# transceiver_and_pulse_generators.net
KiCad netlist of a schematic drawn in EAGLE
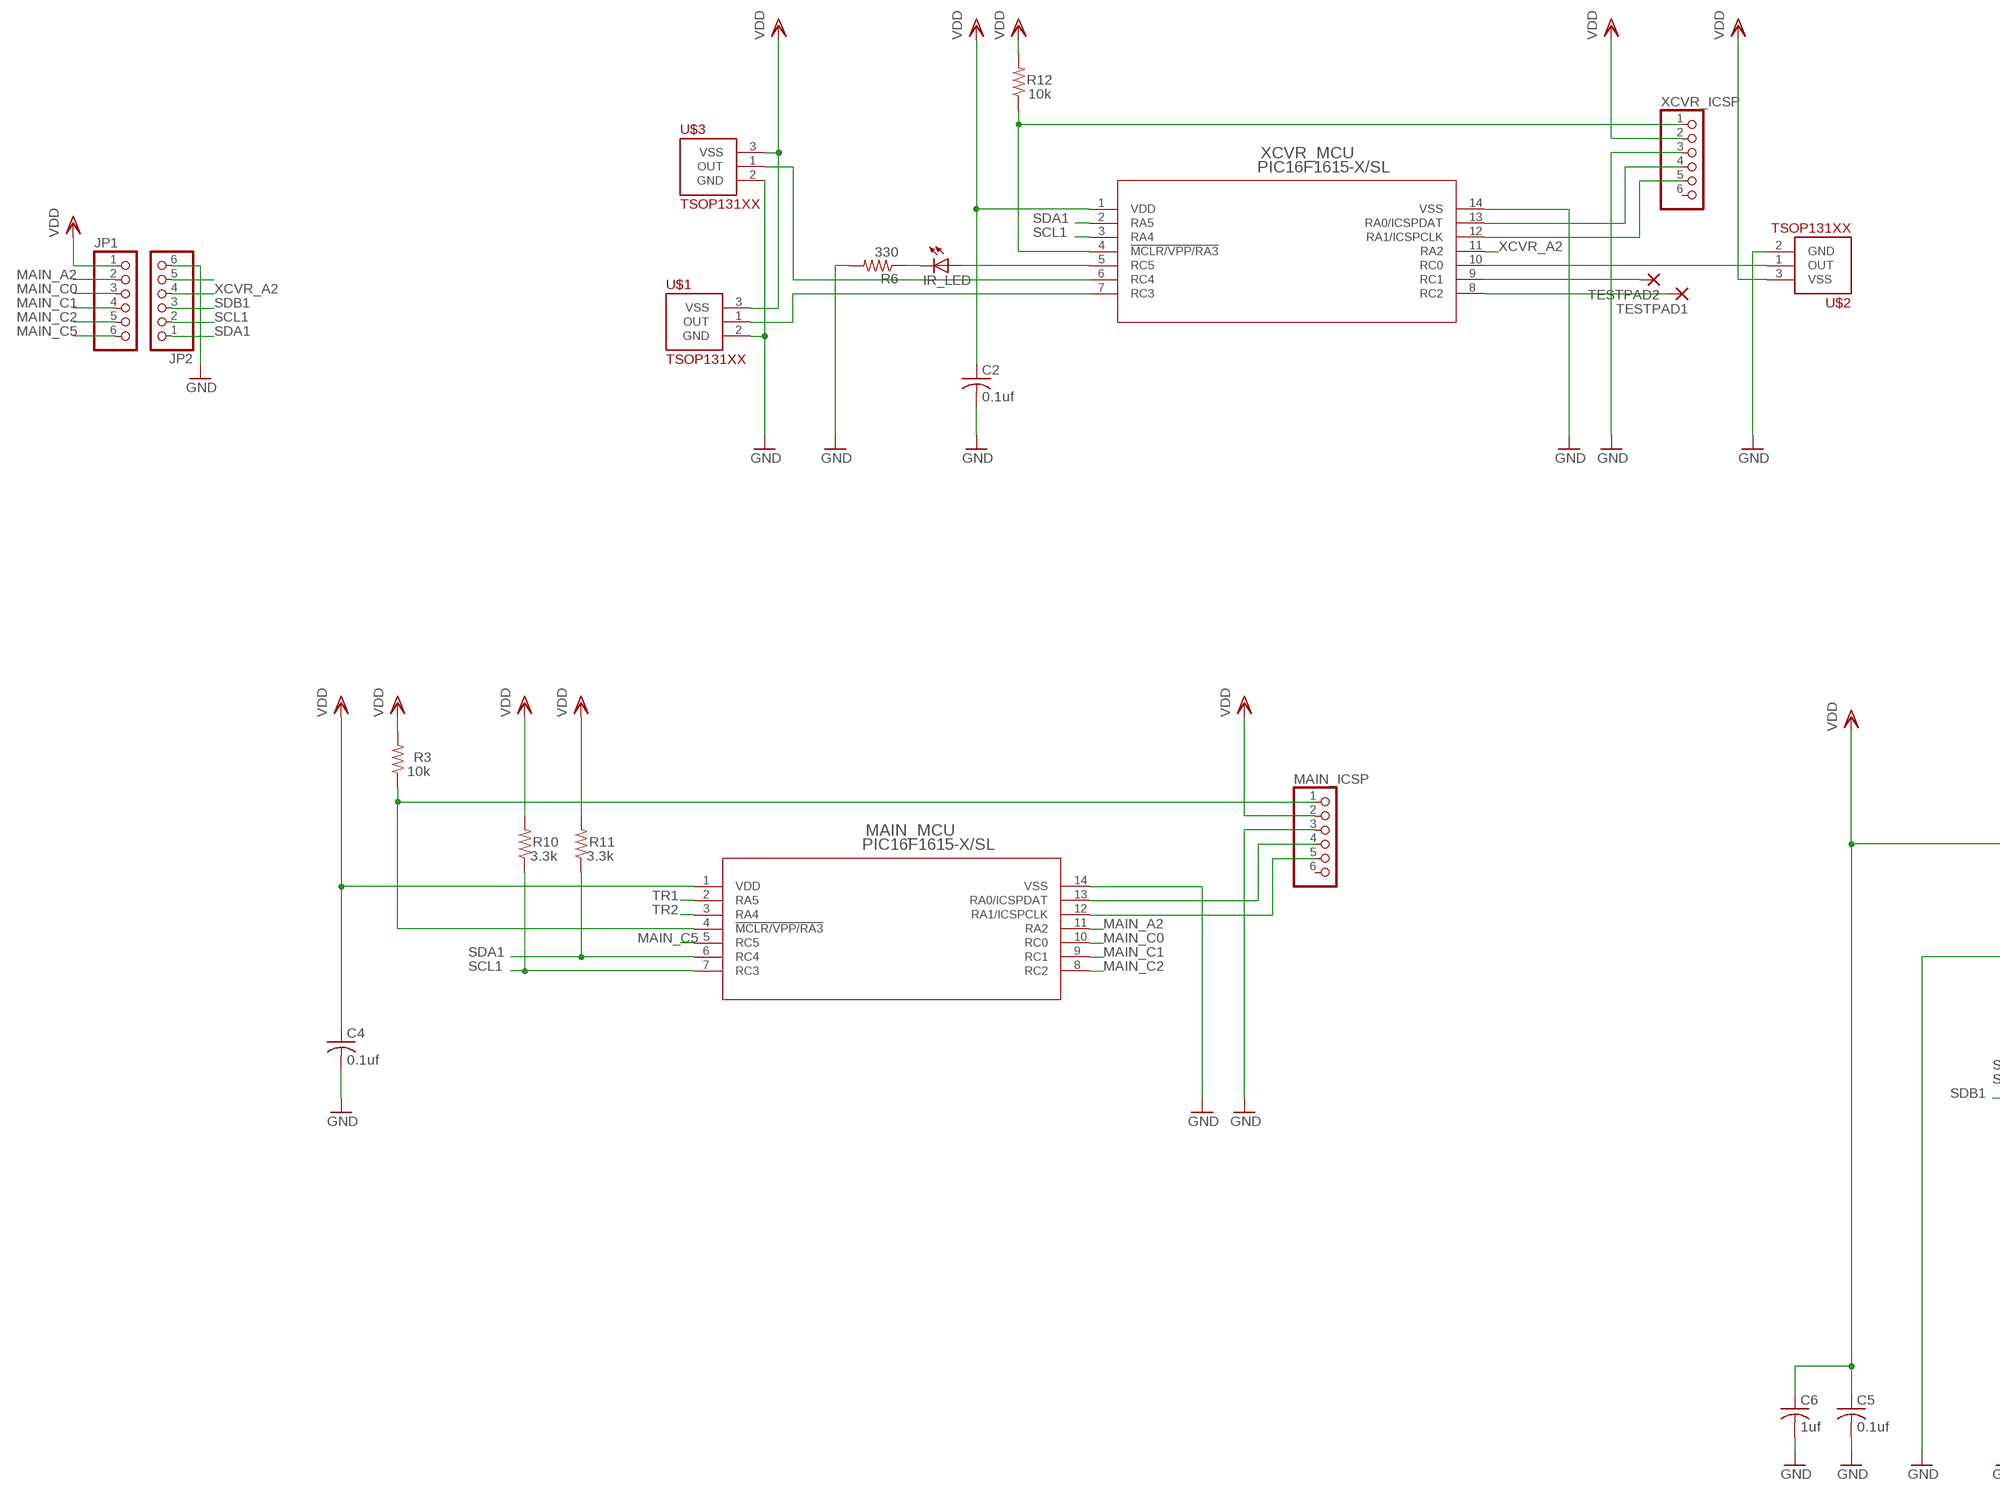
[diagram p0: schematic, sheet 1, part 1 of 2]
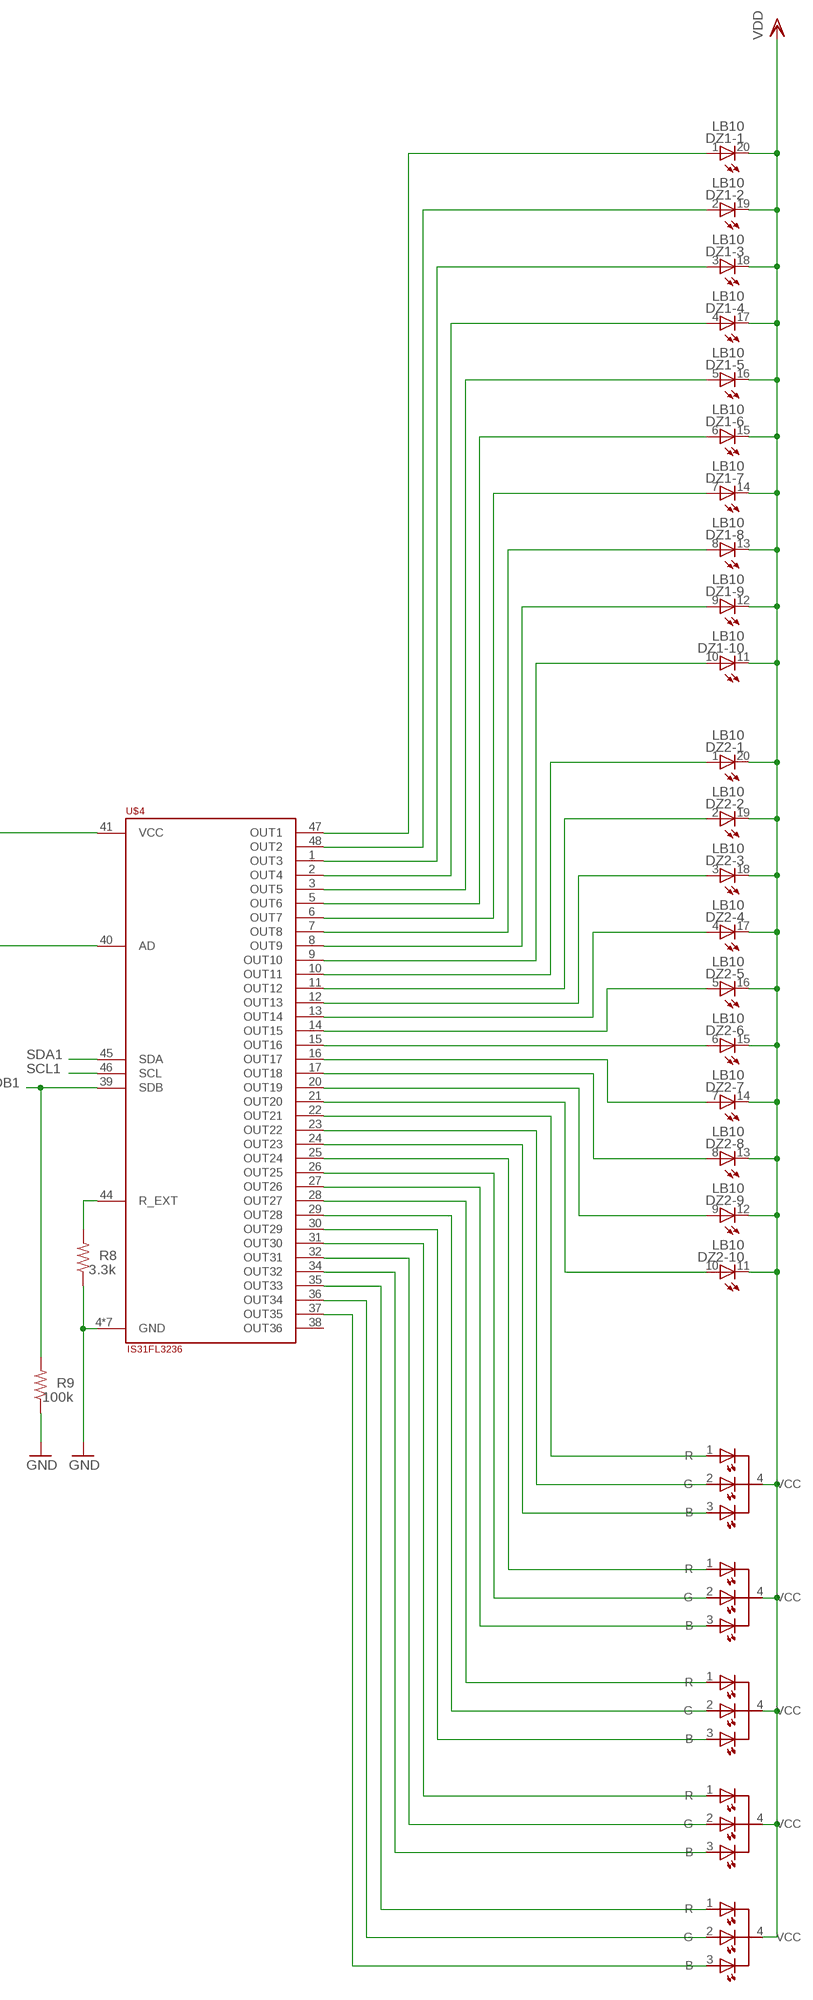
[diagram p1: schematic, sheet 1, part 2 of 2]
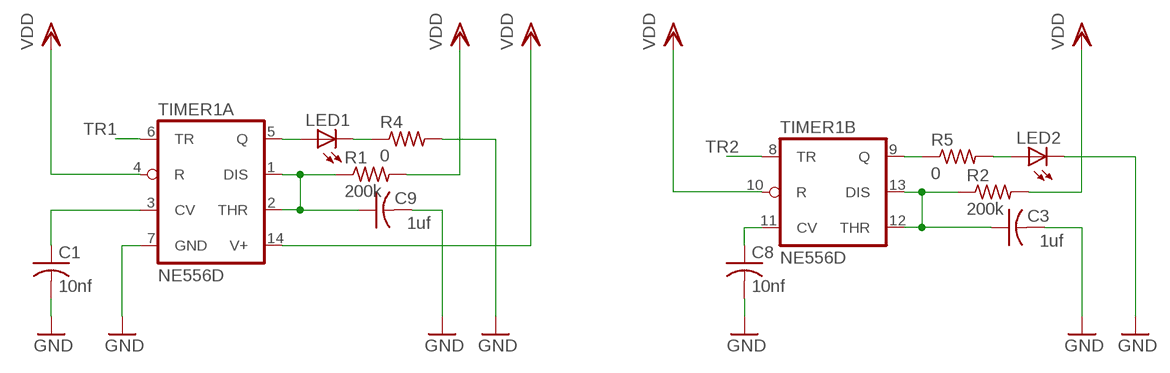
[diagram p2: schematic, sheet 2]

(export (version "E")
  (design (tool "Eeschema 10.0.6"))
  (components
    (comp (ref "C1")
      (value "10nf")
      (footprint "eagle-import:C0603")
      (libsource (lib "eagle-import") (part "C-USC0603"))
    )
    (comp (ref "C3")
      (value "1uf")
      (footprint "eagle-import:C0603")
      (libsource (lib "eagle-import") (part "C-USC0603"))
    )
    (comp (ref "C8")
      (value "10nf")
      (footprint "eagle-import:C0603")
      (libsource (lib "eagle-import") (part "C-USC0603"))
    )
    (comp (ref "C9")
      (value "1uf")
      (footprint "eagle-import:C0603")
      (libsource (lib "eagle-import") (part "C-USC0603"))
    )
    (comp (ref "LED1")
      (value "LED5MM")
      (footprint "eagle-import:LED5MM")
      (libsource (lib "eagle-import") (part "LED5MM"))
    )
    (comp (ref "LED2")
      (value "LED5MM")
      (footprint "eagle-import:LED5MM")
      (libsource (lib "eagle-import") (part "LED5MM"))
    )
    (comp (ref "R1")
      (value "200k")
      (footprint "eagle-import:R0603")
      (libsource (lib "eagle-import") (part "R-US_R0603"))
    )
    (comp (ref "R2")
      (value "200k")
      (footprint "eagle-import:R0603")
      (libsource (lib "eagle-import") (part "R-US_R0603"))
    )
    (comp (ref "R4")
      (value "0")
      (footprint "eagle-import:R0603")
      (libsource (lib "eagle-import") (part "R-US_R0603"))
    )
    (comp (ref "R5")
      (value "0")
      (footprint "eagle-import:R0603")
      (libsource (lib "eagle-import") (part "R-US_R0603"))
    )
    (comp (ref "TIMER1")
      (value "NE556D")
      (footprint "eagle-import:SO14")
      (libsource (lib "eagle-import") (part "556DNE"))
    )
    (comp (ref "C2")
      (value "0.1uf")
      (footprint "eagle-import:C0603")
      (libsource (lib "eagle-import") (part "C-USC0603"))
    )
    (comp (ref "C4")
      (value "0.1uf")
      (footprint "eagle-import:C0603")
      (libsource (lib "eagle-import") (part "C-USC0603"))
    )
    (comp (ref "C5")
      (value "0.1uf")
      (footprint "eagle-import:C0603")
      (libsource (lib "eagle-import") (part "C-USC0603"))
    )
    (comp (ref "C6")
      (value "1uf")
      (footprint "eagle-import:C0603")
      (libsource (lib "eagle-import") (part "C-USC0603"))
    )
    (comp (ref "DZ1")
      (value "LB10")
      (footprint "eagle-import:LB10")
      (libsource (lib "eagle-import") (part "LB10"))
    )
    (comp (ref "DZ2")
      (value "LB10")
      (footprint "eagle-import:LB10")
      (libsource (lib "eagle-import") (part "LB10"))
    )
    (comp (ref "IR_LED")
      (value "LED5MM")
      (footprint "eagle-import:LED5MM")
      (libsource (lib "eagle-import") (part "LED5MM"))
    )
    (comp (ref "JP1")
      (value "PINHD-1X6")
      (footprint "eagle-import:1X06")
      (libsource (lib "eagle-import") (part "PINHD-1X6"))
    )
    (comp (ref "JP2")
      (value "PINHD-1X6")
      (footprint "eagle-import:1X06")
      (libsource (lib "eagle-import") (part "PINHD-1X6"))
    )
    (comp (ref "MAIN_ICSP")
      (value "PINHD-1X6")
      (footprint "eagle-import:1X06")
      (libsource (lib "eagle-import") (part "PINHD-1X6"))
    )
    (comp (ref "MAIN_MCU")
      (value "PIC16F1615-X/SL")
      (footprint "eagle-import:SOIC14_SL")
      (fields (field (name "MANUFACTURER_PART_NUMBER") "pic16f1615xsl"))
      (libsource (lib "eagle-import") (part "PIC16F1615-X/SL"))
    )
    (comp (ref "R3")
      (value "10k")
      (footprint "eagle-import:R0603")
      (libsource (lib "eagle-import") (part "R-US_R0603"))
    )
    (comp (ref "R6")
      (value "330")
      (footprint "eagle-import:R0603")
      (libsource (lib "eagle-import") (part "R-US_R0603"))
    )
    (comp (ref "R8")
      (value "3.3k")
      (footprint "eagle-import:R0603")
      (libsource (lib "eagle-import") (part "R-US_R0603"))
    )
    (comp (ref "R9")
      (value "100k")
      (footprint "eagle-import:R0603")
      (libsource (lib "eagle-import") (part "R-US_R0603"))
    )
    (comp (ref "R10")
      (value "3.3k")
      (footprint "eagle-import:R0603")
      (libsource (lib "eagle-import") (part "R-US_R0603"))
    )
    (comp (ref "R11")
      (value "3.3k")
      (footprint "eagle-import:R0603")
      (libsource (lib "eagle-import") (part "R-US_R0603"))
    )
    (comp (ref "R12")
      (value "10k")
      (footprint "eagle-import:R0603")
      (libsource (lib "eagle-import") (part "R-US_R0603"))
    )
    (comp (ref "TESTPAD1")
      (value "SMD2")
      (footprint "eagle-import:SMD1,27-2,54")
      (libsource (lib "eagle-import") (part "SMD2"))
    )
    (comp (ref "TESTPAD2")
      (value "SMD2")
      (footprint "eagle-import:SMD1,27-2,54")
      (libsource (lib "eagle-import") (part "SMD2"))
    )
    (comp (ref "U$1")
      (value "TSOP131XX")
      (footprint "eagle-import:TSOP13XXX")
      (libsource (lib "eagle-import") (part "TSOP131XX"))
    )
    (comp (ref "U$2")
      (value "TSOP131XX")
      (footprint "eagle-import:TSOP13XXX")
      (libsource (lib "eagle-import") (part "TSOP131XX"))
    )
    (comp (ref "U$3")
      (value "TSOP131XX")
      (footprint "eagle-import:TSOP13XXX")
      (libsource (lib "eagle-import") (part "TSOP131XX"))
    )
    (comp (ref "U$4")
      (value "IS31FL3236")
      (footprint "eagle-import:IS31FL3236")
      (libsource (lib "eagle-import") (part "IS31FL3236"))
    )
    (comp (ref "U$5")
      (value "LTST-C19HE1WT")
      (footprint "eagle-import:LTST-C19HE1WT")
      (libsource (lib "eagle-import") (part "LTST-C19HE1WT"))
    )
    (comp (ref "U$6")
      (value "LTST-C19HE1WT")
      (footprint "eagle-import:LTST-C19HE1WT")
      (libsource (lib "eagle-import") (part "LTST-C19HE1WT"))
    )
    (comp (ref "U$7")
      (value "LTST-C19HE1WT")
      (footprint "eagle-import:LTST-C19HE1WT")
      (libsource (lib "eagle-import") (part "LTST-C19HE1WT"))
    )
    (comp (ref "U$8")
      (value "LTST-C19HE1WT")
      (footprint "eagle-import:LTST-C19HE1WT")
      (libsource (lib "eagle-import") (part "LTST-C19HE1WT"))
    )
    (comp (ref "U$9")
      (value "LTST-C19HE1WT")
      (footprint "eagle-import:LTST-C19HE1WT")
      (libsource (lib "eagle-import") (part "LTST-C19HE1WT"))
    )
    (comp (ref "XCVR_ICSP")
      (value "PINHD-1X6")
      (footprint "eagle-import:1X06")
      (libsource (lib "eagle-import") (part "PINHD-1X6"))
    )
    (comp (ref "XCVR_MCU")
      (value "PIC16F1615-X/SL")
      (footprint "eagle-import:SOIC14_SL")
      (fields (field (name "MANUFACTURER_PART_NUMBER") "pic16f1615xsl"))
      (libsource (lib "eagle-import") (part "PIC16F1615-X/SL"))
    )
  )
  (nets
    (net (code "1") (name "GND") (class "Default")
      (node (ref "C1") (pin "2") (pinfunction "2_2") (pintype "passive"))
      (node (ref "C2") (pin "2") (pinfunction "2_2") (pintype "passive"))
      (node (ref "C3") (pin "2") (pinfunction "2_2") (pintype "passive"))
      (node (ref "C4") (pin "2") (pinfunction "2_2") (pintype "passive"))
      (node (ref "C5") (pin "2") (pinfunction "2_2") (pintype "passive"))
      (node (ref "C6") (pin "2") (pinfunction "2_2") (pintype "passive"))
      (node (ref "C8") (pin "2") (pinfunction "2_2") (pintype "passive"))
      (node (ref "C9") (pin "2") (pinfunction "2_2") (pintype "passive"))
      (node (ref "JP2") (pin "6") (pinfunction "6_6") (pintype "passive"))
      (node (ref "LED2") (pin "K") (pinfunction "C_K") (pintype "passive"))
      (node (ref "MAIN_ICSP") (pin "3") (pinfunction "3_3") (pintype "passive"))
      (node (ref "MAIN_MCU") (pin "14") (pinfunction "VSS_14") (pintype "power_in"))
      (node (ref "R4") (pin "2") (pinfunction "2_2") (pintype "passive"))
      (node (ref "R6") (pin "2") (pinfunction "2_2") (pintype "passive"))
      (node (ref "R8") (pin "1") (pinfunction "1_1") (pintype "passive"))
      (node (ref "R9") (pin "1") (pinfunction "1_1") (pintype "passive"))
      (node (ref "TIMER1") (pin "7") (pinfunction "GND_7") (pintype "power_in"))
      (node (ref "U$1") (pin "2") (pinfunction "GND_2") (pintype "bidirectional"))
      (node (ref "U$2") (pin "2") (pinfunction "GND_2") (pintype "bidirectional"))
      (node (ref "U$3") (pin "2") (pinfunction "GND_2") (pintype "bidirectional"))
      (node (ref "U$4") (pin "18") (pinfunction "GND_18") (pintype "bidirectional"))
      (node (ref "U$4") (pin "19") (pinfunction "GND_19") (pintype "bidirectional"))
      (node (ref "U$4") (pin "33") (pinfunction "GND_33") (pintype "bidirectional"))
      (node (ref "U$4") (pin "4") (pinfunction "GND_4") (pintype "bidirectional"))
      (node (ref "U$4") (pin "40") (pinfunction "AD_40") (pintype "bidirectional"))
      (node (ref "U$4") (pin "42") (pinfunction "GND_42") (pintype "bidirectional"))
      (node (ref "U$4") (pin "43") (pinfunction "GND_43") (pintype "bidirectional"))
      (node (ref "U$4") (pin "49") (pinfunction "GND_49") (pintype "bidirectional"))
      (node (ref "XCVR_ICSP") (pin "3") (pinfunction "3_3") (pintype "passive"))
      (node (ref "XCVR_MCU") (pin "14") (pinfunction "VSS_14") (pintype "power_in"))
    )
    (net (code "2") (name "MAIN_A2") (class "Default")
      (node (ref "JP1") (pin "2") (pinfunction "2_2") (pintype "passive"))
      (node (ref "MAIN_MCU") (pin "11") (pinfunction "RA2_11") (pintype "bidirectional"))
    )
    (net (code "3") (name "MAIN_C0") (class "Default")
      (node (ref "JP1") (pin "3") (pinfunction "3_3") (pintype "passive"))
      (node (ref "MAIN_MCU") (pin "10") (pinfunction "RC0_10") (pintype "bidirectional"))
    )
    (net (code "4") (name "MAIN_C1") (class "Default")
      (node (ref "JP1") (pin "4") (pinfunction "4_4") (pintype "passive"))
      (node (ref "MAIN_MCU") (pin "9") (pinfunction "RC1_9") (pintype "bidirectional"))
    )
    (net (code "5") (name "MAIN_C2") (class "Default")
      (node (ref "JP1") (pin "5") (pinfunction "5_5") (pintype "passive"))
      (node (ref "MAIN_MCU") (pin "8") (pinfunction "RC2_8") (pintype "bidirectional"))
    )
    (net (code "6") (name "MAIN_C5") (class "Default")
      (node (ref "JP1") (pin "6") (pinfunction "6_6") (pintype "passive"))
      (node (ref "MAIN_MCU") (pin "5") (pinfunction "RC5_5") (pintype "bidirectional"))
    )
    (net (code "7") (name "Net-(DZ1A-A)") (class "Default")
      (node (ref "DZ1") (pin "1") (pinfunction "A_1") (pintype "passive"))
      (node (ref "U$4") (pin "47") (pinfunction "OUT1_47") (pintype "bidirectional"))
    )
    (net (code "8") (name "Net-(DZ1B-A)") (class "Default")
      (node (ref "DZ1") (pin "10") (pinfunction "A_10") (pintype "passive"))
      (node (ref "U$4") (pin "9") (pinfunction "OUT10_9") (pintype "bidirectional"))
    )
    (net (code "9") (name "Net-(DZ1C-A)") (class "Default")
      (node (ref "DZ1") (pin "2") (pinfunction "A_2") (pintype "passive"))
      (node (ref "U$4") (pin "48") (pinfunction "OUT2_48") (pintype "bidirectional"))
    )
    (net (code "10") (name "Net-(DZ1D-A)") (class "Default")
      (node (ref "DZ1") (pin "3") (pinfunction "A_3") (pintype "passive"))
      (node (ref "U$4") (pin "1") (pinfunction "OUT3_1") (pintype "bidirectional"))
    )
    (net (code "11") (name "Net-(DZ1E-A)") (class "Default")
      (node (ref "DZ1") (pin "4") (pinfunction "A_4") (pintype "passive"))
      (node (ref "U$4") (pin "2") (pinfunction "OUT4_2") (pintype "bidirectional"))
    )
    (net (code "12") (name "Net-(DZ1F-A)") (class "Default")
      (node (ref "DZ1") (pin "5") (pinfunction "A_5") (pintype "passive"))
      (node (ref "U$4") (pin "3") (pinfunction "OUT5_3") (pintype "bidirectional"))
    )
    (net (code "13") (name "Net-(DZ1G-A)") (class "Default")
      (node (ref "DZ1") (pin "6") (pinfunction "A_6") (pintype "passive"))
      (node (ref "U$4") (pin "5") (pinfunction "OUT6_5") (pintype "bidirectional"))
    )
    (net (code "14") (name "Net-(DZ1H-A)") (class "Default")
      (node (ref "DZ1") (pin "7") (pinfunction "A_7") (pintype "passive"))
      (node (ref "U$4") (pin "6") (pinfunction "OUT7_6") (pintype "bidirectional"))
    )
    (net (code "15") (name "Net-(DZ1I-A)") (class "Default")
      (node (ref "DZ1") (pin "8") (pinfunction "A_8") (pintype "passive"))
      (node (ref "U$4") (pin "7") (pinfunction "OUT8_7") (pintype "bidirectional"))
    )
    (net (code "16") (name "Net-(DZ1J-A)") (class "Default")
      (node (ref "DZ1") (pin "9") (pinfunction "A_9") (pintype "passive"))
      (node (ref "U$4") (pin "8") (pinfunction "OUT9_8") (pintype "bidirectional"))
    )
    (net (code "17") (name "Net-(DZ2A-A)") (class "Default")
      (node (ref "DZ2") (pin "1") (pinfunction "A_1") (pintype "passive"))
      (node (ref "U$4") (pin "10") (pinfunction "OUT11_10") (pintype "bidirectional"))
    )
    (net (code "18") (name "Net-(DZ2B-A)") (class "Default")
      (node (ref "DZ2") (pin "10") (pinfunction "A_10") (pintype "passive"))
      (node (ref "U$4") (pin "21") (pinfunction "OUT20_21") (pintype "bidirectional"))
    )
    (net (code "19") (name "Net-(DZ2C-A)") (class "Default")
      (node (ref "DZ2") (pin "2") (pinfunction "A_2") (pintype "passive"))
      (node (ref "U$4") (pin "11") (pinfunction "OUT12_11") (pintype "bidirectional"))
    )
    (net (code "20") (name "Net-(DZ2D-A)") (class "Default")
      (node (ref "DZ2") (pin "3") (pinfunction "A_3") (pintype "passive"))
      (node (ref "U$4") (pin "12") (pinfunction "OUT13_12") (pintype "bidirectional"))
    )
    (net (code "21") (name "Net-(DZ2E-A)") (class "Default")
      (node (ref "DZ2") (pin "4") (pinfunction "A_4") (pintype "passive"))
      (node (ref "U$4") (pin "13") (pinfunction "OUT14_13") (pintype "bidirectional"))
    )
    (net (code "22") (name "Net-(DZ2F-A)") (class "Default")
      (node (ref "DZ2") (pin "5") (pinfunction "A_5") (pintype "passive"))
      (node (ref "U$4") (pin "14") (pinfunction "OUT15_14") (pintype "bidirectional"))
    )
    (net (code "23") (name "Net-(DZ2G-A)") (class "Default")
      (node (ref "DZ2") (pin "6") (pinfunction "A_6") (pintype "passive"))
      (node (ref "U$4") (pin "15") (pinfunction "OUT16_15") (pintype "bidirectional"))
    )
    (net (code "24") (name "Net-(DZ2H-A)") (class "Default")
      (node (ref "DZ2") (pin "7") (pinfunction "A_7") (pintype "passive"))
      (node (ref "U$4") (pin "16") (pinfunction "OUT17_16") (pintype "bidirectional"))
    )
    (net (code "25") (name "Net-(DZ2I-A)") (class "Default")
      (node (ref "DZ2") (pin "8") (pinfunction "A_8") (pintype "passive"))
      (node (ref "U$4") (pin "17") (pinfunction "OUT18_17") (pintype "bidirectional"))
    )
    (net (code "26") (name "Net-(DZ2J-A)") (class "Default")
      (node (ref "DZ2") (pin "9") (pinfunction "A_9") (pintype "passive"))
      (node (ref "U$4") (pin "20") (pinfunction "OUT19_20") (pintype "bidirectional"))
    )
    (net (code "27") (name "Net-(IR_LED-C)") (class "Default")
      (node (ref "IR_LED") (pin "K") (pinfunction "C_K") (pintype "passive"))
      (node (ref "R6") (pin "1") (pinfunction "1_1") (pintype "passive"))
    )
    (net (code "28") (name "Net-(LED1-C)") (class "Default")
      (node (ref "LED1") (pin "K") (pinfunction "C_K") (pintype "passive"))
      (node (ref "R4") (pin "1") (pinfunction "1_1") (pintype "passive"))
    )
    (net (code "29") (name "Net-(LED2-PadA)") (class "Default")
      (node (ref "LED2") (pin "A") (pinfunction "A_A") (pintype "passive"))
      (node (ref "R5") (pin "2") (pinfunction "2_2") (pintype "passive"))
    )
    (net (code "30") (name "Net-(MAIN_MCU-RA0{slash}ICSPDAT)") (class "Default")
      (node (ref "MAIN_ICSP") (pin "4") (pinfunction "4_4") (pintype "passive"))
      (node (ref "MAIN_MCU") (pin "13") (pinfunction "RA0/ICSPDAT_13") (pintype "bidirectional"))
    )
    (net (code "31") (name "Net-(MAIN_MCU-RA1{slash}ICSPCLK)") (class "Default")
      (node (ref "MAIN_ICSP") (pin "5") (pinfunction "5_5") (pintype "passive"))
      (node (ref "MAIN_MCU") (pin "12") (pinfunction "RA1/ICSPCLK_12") (pintype "bidirectional"))
    )
    (net (code "32") (name "Net-(MAIN_MCU-~{MCLR{slash}VPP{slash}RA3})") (class "Default")
      (node (ref "MAIN_ICSP") (pin "1") (pinfunction "1_1") (pintype "passive"))
      (node (ref "MAIN_MCU") (pin "4") (pinfunction "~{MCLR/VPP/RA3}_4") (pintype "bidirectional"))
      (node (ref "R3") (pin "1") (pinfunction "1_1") (pintype "passive"))
    )
    (net (code "33") (name "Net-(TESTPAD1-P)") (class "Default")
      (node (ref "TESTPAD1") (pin "1") (pinfunction "P_1") (pintype "passive"))
      (node (ref "XCVR_MCU") (pin "8") (pinfunction "RC2_8") (pintype "bidirectional"))
    )
    (net (code "34") (name "Net-(TESTPAD2-P)") (class "Default")
      (node (ref "TESTPAD2") (pin "1") (pinfunction "P_1") (pintype "passive"))
      (node (ref "XCVR_MCU") (pin "9") (pinfunction "RC1_9") (pintype "bidirectional"))
    )
    (net (code "35") (name "Net-(TIMER1A-CV)") (class "Default")
      (node (ref "C1") (pin "1") (pinfunction "1_1") (pintype "passive"))
      (node (ref "TIMER1") (pin "3") (pinfunction "CV_3") (pintype "input"))
    )
    (net (code "36") (name "Net-(TIMER1A-DIS)") (class "Default")
      (node (ref "C9") (pin "1") (pinfunction "1_1") (pintype "passive"))
      (node (ref "R1") (pin "1") (pinfunction "1_1") (pintype "passive"))
      (node (ref "TIMER1") (pin "1") (pinfunction "DIS_1") (pintype "input"))
      (node (ref "TIMER1") (pin "2") (pinfunction "THR_2") (pintype "input"))
    )
    (net (code "37") (name "Net-(TIMER1A-Q)") (class "Default")
      (node (ref "LED1") (pin "A") (pinfunction "A_A") (pintype "passive"))
      (node (ref "TIMER1") (pin "5") (pinfunction "Q_5") (pintype "output"))
    )
    (net (code "38") (name "Net-(TIMER1B-CV)") (class "Default")
      (node (ref "C8") (pin "1") (pinfunction "1_1") (pintype "passive"))
      (node (ref "TIMER1") (pin "11") (pinfunction "CV_11") (pintype "input"))
    )
    (net (code "39") (name "Net-(TIMER1B-DIS)") (class "Default")
      (node (ref "C3") (pin "1") (pinfunction "1_1") (pintype "passive"))
      (node (ref "R2") (pin "1") (pinfunction "1_1") (pintype "passive"))
      (node (ref "TIMER1") (pin "12") (pinfunction "THR_12") (pintype "input"))
      (node (ref "TIMER1") (pin "13") (pinfunction "DIS_13") (pintype "input"))
    )
    (net (code "40") (name "Net-(TIMER1B-Q)") (class "Default")
      (node (ref "R5") (pin "1") (pinfunction "1_1") (pintype "passive"))
      (node (ref "TIMER1") (pin "9") (pinfunction "Q_9") (pintype "output"))
    )
    (net (code "41") (name "Net-(U$1-OUT)") (class "Default")
      (node (ref "U$1") (pin "1") (pinfunction "OUT_1") (pintype "bidirectional"))
      (node (ref "XCVR_MCU") (pin "7") (pinfunction "RC3_7") (pintype "bidirectional"))
    )
    (net (code "42") (name "Net-(U$2-OUT)") (class "Default")
      (node (ref "U$2") (pin "1") (pinfunction "OUT_1") (pintype "bidirectional"))
      (node (ref "XCVR_MCU") (pin "10") (pinfunction "RC0_10") (pintype "bidirectional"))
    )
    (net (code "43") (name "Net-(U$3-OUT)") (class "Default")
      (node (ref "U$3") (pin "1") (pinfunction "OUT_1") (pintype "bidirectional"))
      (node (ref "XCVR_MCU") (pin "6") (pinfunction "RC4_6") (pintype "bidirectional"))
    )
    (net (code "44") (name "Net-(U$4-OUT21)") (class "Default")
      (node (ref "U$4") (pin "22") (pinfunction "OUT21_22") (pintype "bidirectional"))
      (node (ref "U$5") (pin "1") (pinfunction "R_1") (pintype "bidirectional"))
    )
    (net (code "45") (name "Net-(U$4-OUT22)") (class "Default")
      (node (ref "U$4") (pin "23") (pinfunction "OUT22_23") (pintype "bidirectional"))
      (node (ref "U$5") (pin "2") (pinfunction "G_2") (pintype "bidirectional"))
    )
    (net (code "46") (name "Net-(U$4-OUT23)") (class "Default")
      (node (ref "U$4") (pin "24") (pinfunction "OUT23_24") (pintype "bidirectional"))
      (node (ref "U$5") (pin "3") (pinfunction "B_3") (pintype "bidirectional"))
    )
    (net (code "47") (name "Net-(U$4-OUT24)") (class "Default")
      (node (ref "U$4") (pin "25") (pinfunction "OUT24_25") (pintype "bidirectional"))
      (node (ref "U$6") (pin "1") (pinfunction "R_1") (pintype "bidirectional"))
    )
    (net (code "48") (name "Net-(U$4-OUT25)") (class "Default")
      (node (ref "U$4") (pin "26") (pinfunction "OUT25_26") (pintype "bidirectional"))
      (node (ref "U$6") (pin "2") (pinfunction "G_2") (pintype "bidirectional"))
    )
    (net (code "49") (name "Net-(U$4-OUT26)") (class "Default")
      (node (ref "U$4") (pin "27") (pinfunction "OUT26_27") (pintype "bidirectional"))
      (node (ref "U$6") (pin "3") (pinfunction "B_3") (pintype "bidirectional"))
    )
    (net (code "50") (name "Net-(U$4-OUT27)") (class "Default")
      (node (ref "U$4") (pin "28") (pinfunction "OUT27_28") (pintype "bidirectional"))
      (node (ref "U$7") (pin "1") (pinfunction "R_1") (pintype "bidirectional"))
    )
    (net (code "51") (name "Net-(U$4-OUT28)") (class "Default")
      (node (ref "U$4") (pin "29") (pinfunction "OUT28_29") (pintype "bidirectional"))
      (node (ref "U$7") (pin "2") (pinfunction "G_2") (pintype "bidirectional"))
    )
    (net (code "52") (name "Net-(U$4-OUT29)") (class "Default")
      (node (ref "U$4") (pin "30") (pinfunction "OUT29_30") (pintype "bidirectional"))
      (node (ref "U$7") (pin "3") (pinfunction "B_3") (pintype "bidirectional"))
    )
    (net (code "53") (name "Net-(U$4-OUT30)") (class "Default")
      (node (ref "U$4") (pin "31") (pinfunction "OUT30_31") (pintype "bidirectional"))
      (node (ref "U$8") (pin "1") (pinfunction "R_1") (pintype "bidirectional"))
    )
    (net (code "54") (name "Net-(U$4-OUT31)") (class "Default")
      (node (ref "U$4") (pin "32") (pinfunction "OUT31_32") (pintype "bidirectional"))
      (node (ref "U$8") (pin "2") (pinfunction "G_2") (pintype "bidirectional"))
    )
    (net (code "55") (name "Net-(U$4-OUT32)") (class "Default")
      (node (ref "U$4") (pin "34") (pinfunction "OUT32_34") (pintype "bidirectional"))
      (node (ref "U$8") (pin "3") (pinfunction "B_3") (pintype "bidirectional"))
    )
    (net (code "56") (name "Net-(U$4-OUT33)") (class "Default")
      (node (ref "U$4") (pin "35") (pinfunction "OUT33_35") (pintype "bidirectional"))
      (node (ref "U$9") (pin "1") (pinfunction "R_1") (pintype "bidirectional"))
    )
    (net (code "57") (name "Net-(U$4-OUT34)") (class "Default")
      (node (ref "U$4") (pin "36") (pinfunction "OUT34_36") (pintype "bidirectional"))
      (node (ref "U$9") (pin "2") (pinfunction "G_2") (pintype "bidirectional"))
    )
    (net (code "58") (name "Net-(U$4-OUT35)") (class "Default")
      (node (ref "U$4") (pin "37") (pinfunction "OUT35_37") (pintype "bidirectional"))
      (node (ref "U$9") (pin "3") (pinfunction "B_3") (pintype "bidirectional"))
    )
    (net (code "59") (name "Net-(U$4-R_EXT)") (class "Default")
      (node (ref "R8") (pin "2") (pinfunction "2_2") (pintype "passive"))
      (node (ref "U$4") (pin "44") (pinfunction "R_EXT_44") (pintype "bidirectional"))
    )
    (net (code "60") (name "Net-(XCVR_MCU-RA0{slash}ICSPDAT)") (class "Default")
      (node (ref "XCVR_ICSP") (pin "4") (pinfunction "4_4") (pintype "passive"))
      (node (ref "XCVR_MCU") (pin "13") (pinfunction "RA0/ICSPDAT_13") (pintype "bidirectional"))
    )
    (net (code "61") (name "Net-(XCVR_MCU-RA1{slash}ICSPCLK)") (class "Default")
      (node (ref "XCVR_ICSP") (pin "5") (pinfunction "5_5") (pintype "passive"))
      (node (ref "XCVR_MCU") (pin "12") (pinfunction "RA1/ICSPCLK_12") (pintype "bidirectional"))
    )
    (net (code "62") (name "Net-(XCVR_MCU-RC5)") (class "Default")
      (node (ref "IR_LED") (pin "A") (pinfunction "A_A") (pintype "passive"))
      (node (ref "XCVR_MCU") (pin "5") (pinfunction "RC5_5") (pintype "bidirectional"))
    )
    (net (code "63") (name "Net-(XCVR_MCU-~{MCLR{slash}VPP{slash}RA3})") (class "Default")
      (node (ref "R12") (pin "1") (pinfunction "1_1") (pintype "passive"))
      (node (ref "XCVR_ICSP") (pin "1") (pinfunction "1_1") (pintype "passive"))
      (node (ref "XCVR_MCU") (pin "4") (pinfunction "~{MCLR/VPP/RA3}_4") (pintype "bidirectional"))
    )
    (net (code "64") (name "SCL1") (class "Default")
      (node (ref "JP2") (pin "2") (pinfunction "2_2") (pintype "passive"))
      (node (ref "MAIN_MCU") (pin "7") (pinfunction "RC3_7") (pintype "bidirectional"))
      (node (ref "R10") (pin "1") (pinfunction "1_1") (pintype "passive"))
      (node (ref "U$4") (pin "46") (pinfunction "SCL_46") (pintype "bidirectional"))
      (node (ref "XCVR_MCU") (pin "3") (pinfunction "RA4_3") (pintype "bidirectional"))
    )
    (net (code "65") (name "SDA1") (class "Default")
      (node (ref "JP2") (pin "1") (pinfunction "1_1") (pintype "passive"))
      (node (ref "MAIN_MCU") (pin "6") (pinfunction "RC4_6") (pintype "bidirectional"))
      (node (ref "R11") (pin "1") (pinfunction "1_1") (pintype "passive"))
      (node (ref "U$4") (pin "45") (pinfunction "SDA_45") (pintype "bidirectional"))
      (node (ref "XCVR_MCU") (pin "2") (pinfunction "RA5_2") (pintype "bidirectional"))
    )
    (net (code "66") (name "SDB1") (class "Default")
      (node (ref "JP2") (pin "3") (pinfunction "3_3") (pintype "passive"))
      (node (ref "R9") (pin "2") (pinfunction "2_2") (pintype "passive"))
      (node (ref "U$4") (pin "39") (pinfunction "SDB_39") (pintype "bidirectional"))
    )
    (net (code "67") (name "TR1") (class "Default")
      (node (ref "MAIN_MCU") (pin "2") (pinfunction "RA5_2") (pintype "bidirectional"))
      (node (ref "TIMER1") (pin "6") (pinfunction "TR_6") (pintype "input"))
    )
    (net (code "68") (name "TR2") (class "Default")
      (node (ref "MAIN_MCU") (pin "3") (pinfunction "RA4_3") (pintype "bidirectional"))
      (node (ref "TIMER1") (pin "8") (pinfunction "TR_8") (pintype "input"))
    )
    (net (code "69") (name "VDD") (class "Default")
      (node (ref "C2") (pin "1") (pinfunction "1_1") (pintype "passive"))
      (node (ref "C4") (pin "1") (pinfunction "1_1") (pintype "passive"))
      (node (ref "C5") (pin "1") (pinfunction "1_1") (pintype "passive"))
      (node (ref "C6") (pin "1") (pinfunction "1_1") (pintype "passive"))
      (node (ref "DZ1") (pin "11") (pinfunction "C_11") (pintype "passive"))
      (node (ref "DZ1") (pin "12") (pinfunction "C_12") (pintype "passive"))
      (node (ref "DZ1") (pin "13") (pinfunction "C_13") (pintype "passive"))
      (node (ref "DZ1") (pin "14") (pinfunction "C_14") (pintype "passive"))
      (node (ref "DZ1") (pin "15") (pinfunction "C_15") (pintype "passive"))
      (node (ref "DZ1") (pin "16") (pinfunction "C_16") (pintype "passive"))
      (node (ref "DZ1") (pin "17") (pinfunction "C_17") (pintype "passive"))
      (node (ref "DZ1") (pin "18") (pinfunction "C_18") (pintype "passive"))
      (node (ref "DZ1") (pin "19") (pinfunction "C_19") (pintype "passive"))
      (node (ref "DZ1") (pin "20") (pinfunction "C_20") (pintype "passive"))
      (node (ref "DZ2") (pin "11") (pinfunction "C_11") (pintype "passive"))
      (node (ref "DZ2") (pin "12") (pinfunction "C_12") (pintype "passive"))
      (node (ref "DZ2") (pin "13") (pinfunction "C_13") (pintype "passive"))
      (node (ref "DZ2") (pin "14") (pinfunction "C_14") (pintype "passive"))
      (node (ref "DZ2") (pin "15") (pinfunction "C_15") (pintype "passive"))
      (node (ref "DZ2") (pin "16") (pinfunction "C_16") (pintype "passive"))
      (node (ref "DZ2") (pin "17") (pinfunction "C_17") (pintype "passive"))
      (node (ref "DZ2") (pin "18") (pinfunction "C_18") (pintype "passive"))
      (node (ref "DZ2") (pin "19") (pinfunction "C_19") (pintype "passive"))
      (node (ref "DZ2") (pin "20") (pinfunction "C_20") (pintype "passive"))
      (node (ref "JP1") (pin "1") (pinfunction "1_1") (pintype "passive"))
      (node (ref "MAIN_ICSP") (pin "2") (pinfunction "2_2") (pintype "passive"))
      (node (ref "MAIN_MCU") (pin "1") (pinfunction "VDD_1") (pintype "power_in"))
      (node (ref "R1") (pin "2") (pinfunction "2_2") (pintype "passive"))
      (node (ref "R10") (pin "2") (pinfunction "2_2") (pintype "passive"))
      (node (ref "R11") (pin "2") (pinfunction "2_2") (pintype "passive"))
      (node (ref "R12") (pin "2") (pinfunction "2_2") (pintype "passive"))
      (node (ref "R2") (pin "2") (pinfunction "2_2") (pintype "passive"))
      (node (ref "R3") (pin "2") (pinfunction "2_2") (pintype "passive"))
      (node (ref "TIMER1") (pin "10") (pinfunction "R_10") (pintype "input"))
      (node (ref "TIMER1") (pin "14") (pinfunction "V+_14") (pintype "power_in"))
      (node (ref "TIMER1") (pin "4") (pinfunction "R_4") (pintype "input"))
      (node (ref "U$1") (pin "3") (pinfunction "VSS_3") (pintype "bidirectional"))
      (node (ref "U$2") (pin "3") (pinfunction "VSS_3") (pintype "bidirectional"))
      (node (ref "U$3") (pin "3") (pinfunction "VSS_3") (pintype "bidirectional"))
      (node (ref "U$4") (pin "41") (pinfunction "VCC_41") (pintype "bidirectional"))
      (node (ref "U$5") (pin "4") (pinfunction "VCC_4") (pintype "bidirectional"))
      (node (ref "U$6") (pin "4") (pinfunction "VCC_4") (pintype "bidirectional"))
      (node (ref "U$7") (pin "4") (pinfunction "VCC_4") (pintype "bidirectional"))
      (node (ref "U$8") (pin "4") (pinfunction "VCC_4") (pintype "bidirectional"))
      (node (ref "U$9") (pin "4") (pinfunction "VCC_4") (pintype "bidirectional"))
      (node (ref "XCVR_ICSP") (pin "2") (pinfunction "2_2") (pintype "passive"))
      (node (ref "XCVR_MCU") (pin "1") (pinfunction "VDD_1") (pintype "power_in"))
    )
    (net (code "70") (name "XCVR_A2") (class "Default")
      (node (ref "JP2") (pin "4") (pinfunction "4_4") (pintype "passive"))
      (node (ref "XCVR_MCU") (pin "11") (pinfunction "RA2_11") (pintype "bidirectional"))
    )
    (net (code "71") (name "unconnected-(JP2-Pad5)") (class "Default")
      (node (ref "JP2") (pin "5") (pinfunction "5_5") (pintype "passive"))
    )
    (net (code "72") (name "unconnected-(MAIN_ICSP-Pad6)") (class "Default")
      (node (ref "MAIN_ICSP") (pin "6") (pinfunction "6_6") (pintype "passive"))
    )
    (net (code "73") (name "unconnected-(U$4-OUT36-Pad38)") (class "Default")
      (node (ref "U$4") (pin "38") (pinfunction "OUT36_38") (pintype "bidirectional"))
    )
    (net (code "74") (name "unconnected-(XCVR_ICSP-Pad6)") (class "Default")
      (node (ref "XCVR_ICSP") (pin "6") (pinfunction "6_6") (pintype "passive"))
    )
  )
)
